# Debugger.net
KiCad netlist of a schematic drawn in Altium Designer
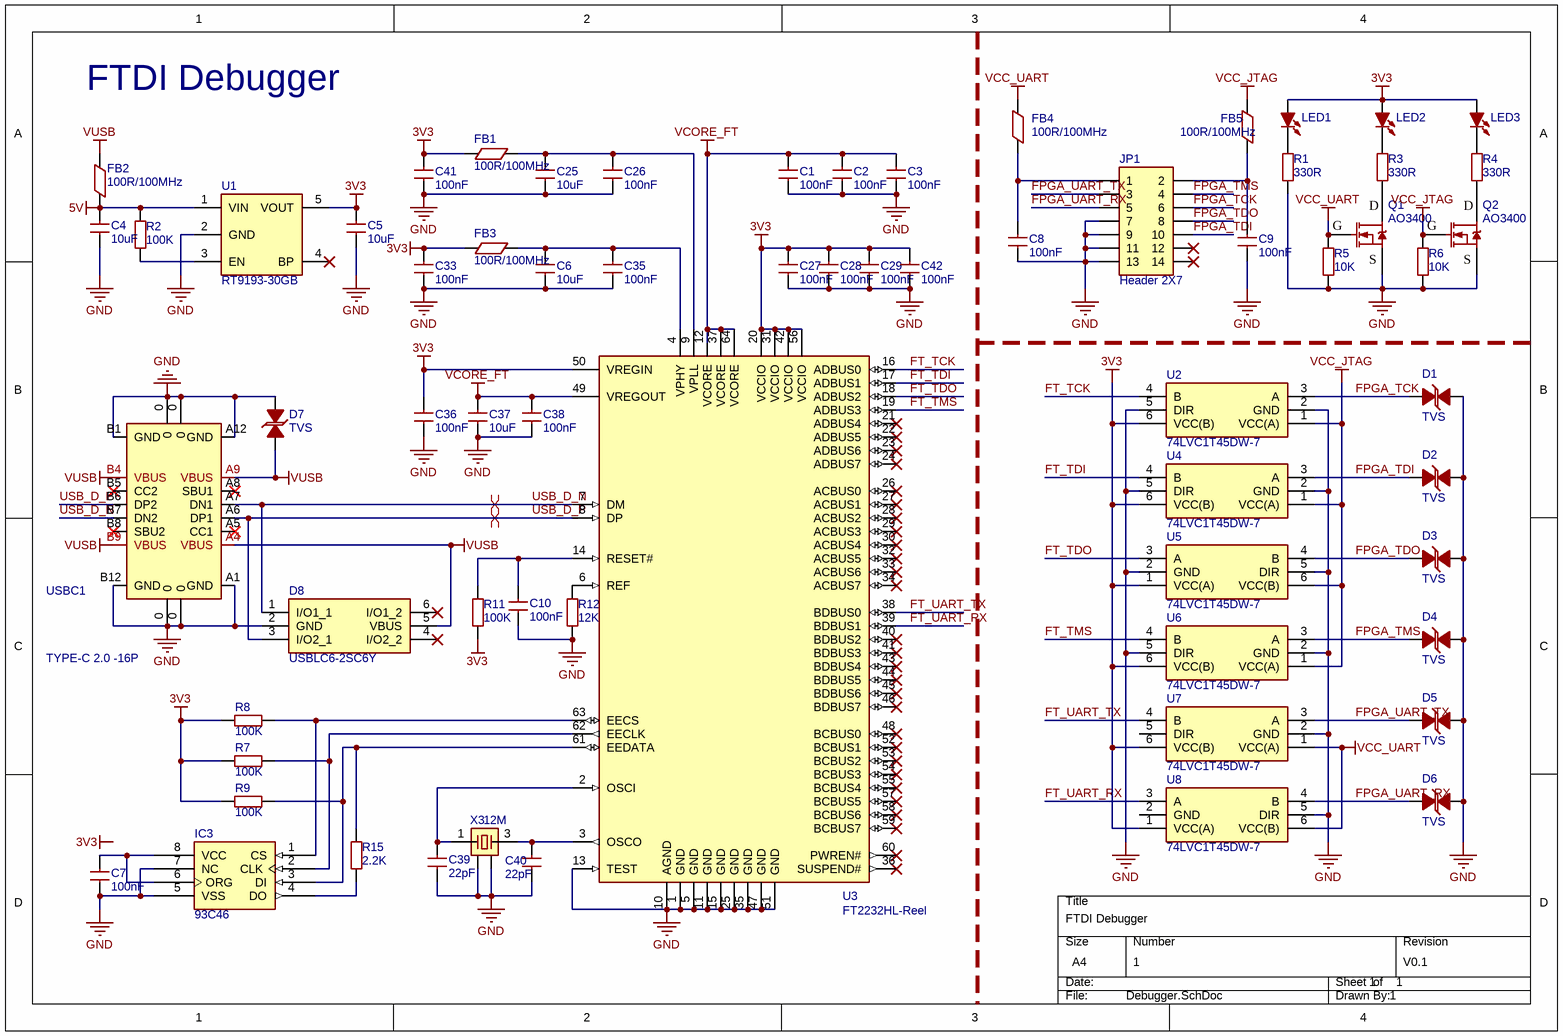
[diagram p0: Debugger.SchDoc]

(export (version "E")
  (design (tool "Eeschema 10.0.6"))
  (components
    (comp (ref "C1")
      (value "100nF")
      (footprint "C0603_NS")
      (description "贴片电容/MLCC电容")
      (libsource (lib "0.1 - 电阻-电容-电感-晶振-晶体-磁珠-电位器-法拉电容-馈通电容") (part "C"))
    )
    (comp (ref "C2")
      (value "100nF")
      (footprint "C0603_NS")
      (description "贴片电容/MLCC电容")
      (libsource (lib "0.1 - 电阻-电容-电感-晶振-晶体-磁珠-电位器-法拉电容-馈通电容") (part "C"))
    )
    (comp (ref "C3")
      (value "100nF")
      (footprint "C0603_NS")
      (description "贴片电容/MLCC电容")
      (libsource (lib "0.1 - 电阻-电容-电感-晶振-晶体-磁珠-电位器-法拉电容-馈通电容") (part "C"))
    )
    (comp (ref "C4")
      (value "10uF")
      (footprint "C0603_NS")
      (description "贴片电容/MLCC电容")
      (libsource (lib "0.1 - 电阻-电容-电感-晶振-晶体-磁珠-电位器-法拉电容-馈通电容") (part "C"))
    )
    (comp (ref "C5")
      (value "10uF")
      (footprint "C0603_NS")
      (description "贴片电容/MLCC电容")
      (libsource (lib "0.1 - 电阻-电容-电感-晶振-晶体-磁珠-电位器-法拉电容-馈通电容") (part "C"))
    )
    (comp (ref "C6")
      (value "10uF")
      (footprint "C0603_NS")
      (description "贴片电容/MLCC电容")
      (libsource (lib "0.1 - 电阻-电容-电感-晶振-晶体-磁珠-电位器-法拉电容-馈通电容") (part "C"))
    )
    (comp (ref "C7")
      (value "100nF")
      (footprint "C0603_NS")
      (description "贴片电容/MLCC电容")
      (libsource (lib "0.1 - 电阻-电容-电感-晶振-晶体-磁珠-电位器-法拉电容-馈通电容") (part "C"))
    )
    (comp (ref "C8")
      (value "100nF")
      (footprint "C0603_NS")
      (description "贴片电容/MLCC电容")
      (libsource (lib "0.1 - 电阻-电容-电感-晶振-晶体-磁珠-电位器-法拉电容-馈通电容") (part "C"))
    )
    (comp (ref "C9")
      (value "100nF")
      (footprint "C0603_NS")
      (description "贴片电容/MLCC电容")
      (libsource (lib "0.1 - 电阻-电容-电感-晶振-晶体-磁珠-电位器-法拉电容-馈通电容") (part "C"))
    )
    (comp (ref "C10")
      (value "100nF")
      (footprint "C0603_NS")
      (description "贴片电容/MLCC电容")
      (libsource (lib "0.1 - 电阻-电容-电感-晶振-晶体-磁珠-电位器-法拉电容-馈通电容") (part "C"))
    )
    (comp (ref "C25")
      (value "10uF")
      (footprint "C0603_NS")
      (description "贴片电容/MLCC电容")
      (libsource (lib "0.1 - 电阻-电容-电感-晶振-晶体-磁珠-电位器-法拉电容-馈通电容") (part "C"))
    )
    (comp (ref "C26")
      (value "100nF")
      (footprint "C0603_NS")
      (description "贴片电容/MLCC电容")
      (libsource (lib "0.1 - 电阻-电容-电感-晶振-晶体-磁珠-电位器-法拉电容-馈通电容") (part "C"))
    )
    (comp (ref "C27")
      (value "100nF")
      (footprint "C0603_NS")
      (description "贴片电容/MLCC电容")
      (libsource (lib "0.1 - 电阻-电容-电感-晶振-晶体-磁珠-电位器-法拉电容-馈通电容") (part "C"))
    )
    (comp (ref "C28")
      (value "100nF")
      (footprint "C0603_NS")
      (description "贴片电容/MLCC电容")
      (libsource (lib "0.1 - 电阻-电容-电感-晶振-晶体-磁珠-电位器-法拉电容-馈通电容") (part "C"))
    )
    (comp (ref "C29")
      (value "100nF")
      (footprint "C0603_NS")
      (description "贴片电容/MLCC电容")
      (libsource (lib "0.1 - 电阻-电容-电感-晶振-晶体-磁珠-电位器-法拉电容-馈通电容") (part "C"))
    )
    (comp (ref "C33")
      (value "100nF")
      (footprint "C0603_NS")
      (description "贴片电容/MLCC电容")
      (libsource (lib "0.1 - 电阻-电容-电感-晶振-晶体-磁珠-电位器-法拉电容-馈通电容") (part "C"))
    )
    (comp (ref "C35")
      (value "100nF")
      (footprint "C0603_NS")
      (description "贴片电容/MLCC电容")
      (libsource (lib "0.1 - 电阻-电容-电感-晶振-晶体-磁珠-电位器-法拉电容-馈通电容") (part "C"))
    )
    (comp (ref "C36")
      (value "100nF")
      (footprint "C0603_NS")
      (description "贴片电容/MLCC电容")
      (libsource (lib "0.1 - 电阻-电容-电感-晶振-晶体-磁珠-电位器-法拉电容-馈通电容") (part "C"))
    )
    (comp (ref "C37")
      (value "10uF")
      (footprint "C0603_NS")
      (description "贴片电容/MLCC电容")
      (libsource (lib "0.1 - 电阻-电容-电感-晶振-晶体-磁珠-电位器-法拉电容-馈通电容") (part "C"))
    )
    (comp (ref "C38")
      (value "100nF")
      (footprint "C0603_NS")
      (description "贴片电容/MLCC电容")
      (libsource (lib "0.1 - 电阻-电容-电感-晶振-晶体-磁珠-电位器-法拉电容-馈通电容") (part "C"))
    )
    (comp (ref "C39")
      (value "22pF")
      (footprint "C0603_NS")
      (description "贴片电容/MLCC电容")
      (libsource (lib "0.1 - 电阻-电容-电感-晶振-晶体-磁珠-电位器-法拉电容-馈通电容") (part "C"))
    )
    (comp (ref "C40")
      (value "22pF")
      (footprint "C0603_NS")
      (description "贴片电容/MLCC电容")
      (libsource (lib "0.1 - 电阻-电容-电感-晶振-晶体-磁珠-电位器-法拉电容-馈通电容") (part "C"))
    )
    (comp (ref "C41")
      (value "100nF")
      (footprint "C0603_NS")
      (description "贴片电容/MLCC电容")
      (libsource (lib "0.1 - 电阻-电容-电感-晶振-晶体-磁珠-电位器-法拉电容-馈通电容") (part "C"))
    )
    (comp (ref "C42")
      (value "100nF")
      (footprint "C0603_NS")
      (description "贴片电容/MLCC电容")
      (libsource (lib "0.1 - 电阻-电容-电感-晶振-晶体-磁珠-电位器-法拉电容-馈通电容") (part "C"))
    )
    (comp (ref "D1")
      (value "TVS")
      (footprint "SOD-123")
      (description "TVS通用")
      (libsource (lib "0.2 - 二极管-TVS-ESD-整流桥-放电管") (part "TVS"))
    )
    (comp (ref "D2")
      (value "TVS")
      (footprint "SOD-123")
      (description "TVS通用")
      (libsource (lib "0.2 - 二极管-TVS-ESD-整流桥-放电管") (part "TVS"))
    )
    (comp (ref "D3")
      (value "TVS")
      (footprint "SOD-123")
      (description "TVS通用")
      (libsource (lib "0.2 - 二极管-TVS-ESD-整流桥-放电管") (part "TVS"))
    )
    (comp (ref "D4")
      (value "TVS")
      (footprint "SOD-123")
      (description "TVS通用")
      (libsource (lib "0.2 - 二极管-TVS-ESD-整流桥-放电管") (part "TVS"))
    )
    (comp (ref "D5")
      (value "TVS")
      (footprint "SOD-123")
      (description "TVS通用")
      (libsource (lib "0.2 - 二极管-TVS-ESD-整流桥-放电管") (part "TVS"))
    )
    (comp (ref "D6")
      (value "TVS")
      (footprint "SOD-123")
      (description "TVS通用")
      (libsource (lib "0.2 - 二极管-TVS-ESD-整流桥-放电管") (part "TVS"))
    )
    (comp (ref "D7")
      (value "TVS")
      (footprint "SOD-123")
      (description "TVS通用")
      (libsource (lib "0.2 - 二极管-TVS-ESD-整流桥-放电管") (part "TVS"))
    )
    (comp (ref "D8")
      (value "USBLC6-2SC6Y")
      (footprint "SamacSys:SOT95P280X145-6N")
      (description "Diode")
      (fields (field (name "MOUSER PART NUMBER") "511-USBLC6-2SC6Y"))
      (libsource (lib "SamacSys") (part "USBLC6-2SC6Y"))
    )
    (comp (ref "FB1")
      (value "100R/100MHz")
      (footprint "R0805_L")
      (description "贴片磁珠")
      (libsource (lib "0.1 - 电阻-电容-电感-晶振-晶体-磁珠-电位器-法拉电容-馈通电容") (part "FB"))
    )
    (comp (ref "FB2")
      (value "100R/100MHz")
      (footprint "R0805_L")
      (description "贴片磁珠")
      (libsource (lib "0.1 - 电阻-电容-电感-晶振-晶体-磁珠-电位器-法拉电容-馈通电容") (part "FB"))
    )
    (comp (ref "FB3")
      (value "100R/100MHz")
      (footprint "R0805_L")
      (description "贴片磁珠")
      (libsource (lib "0.1 - 电阻-电容-电感-晶振-晶体-磁珠-电位器-法拉电容-馈通电容") (part "FB"))
    )
    (comp (ref "FB4")
      (value "100R/100MHz")
      (footprint "R0805_L")
      (description "贴片磁珠")
      (libsource (lib "0.1 - 电阻-电容-电感-晶振-晶体-磁珠-电位器-法拉电容-馈通电容") (part "FB"))
    )
    (comp (ref "FB5")
      (value "100R/100MHz")
      (footprint "R0805_L")
      (description "贴片磁珠")
      (libsource (lib "0.1 - 电阻-电容-电感-晶振-晶体-磁珠-电位器-法拉电容-馈通电容") (part "FB"))
    )
    (comp (ref "IC3")
      (value "93C46")
      (footprint "SOP8_L")
      (description "外置EEPROM")
      (libsource (lib "0.8 - 常见芯片") (part "93C46"))
    )
    (comp (ref "JP1")
      (value "Header 2X7")
      (footprint "HDR2.54-WI-2x7P")
      (description "7*2P接插件")
      (libsource (lib "5.5 - 2.54mm连接器(KF2EDGK_XH2.54_2.54排针排母)") (part "Header 7X2"))
    )
    (comp (ref "LED1")
      (value "红色")
      (footprint "LED0603_R")
      (description "贴片LED")
      (libsource (lib "0.3 - LED发光二极管-IR二极管_接收管-光耦") (part "LED-SMD"))
    )
    (comp (ref "LED2")
      (value "红色")
      (footprint "LED0603_R")
      (description "贴片LED")
      (libsource (lib "0.3 - LED发光二极管-IR二极管_接收管-光耦") (part "LED-SMD"))
    )
    (comp (ref "LED3")
      (value "红色")
      (footprint "LED0603_R")
      (description "贴片LED")
      (libsource (lib "0.3 - LED发光二极管-IR二极管_接收管-光耦") (part "LED-SMD"))
    )
    (comp (ref "Q1")
      (value "AO3400")
      (footprint "SOT23-3N")
      (description "N沟道 30V/4.2A")
      (libsource (lib "0.4 - 三极管-场效应管-可控硅") (part "AO3400"))
    )
    (comp (ref "Q2")
      (value "AO3400")
      (footprint "SOT23-3N")
      (description "N沟道 30V/4.2A")
      (libsource (lib "0.4 - 三极管-场效应管-可控硅") (part "AO3400"))
    )
    (comp (ref "R1")
      (value "330R")
      (footprint "R0603_NS")
      (description "贴片电阻")
      (libsource (lib "0.1 - 电阻-电容-电感-晶振-晶体-磁珠-电位器-法拉电容-馈通电容") (part "R"))
    )
    (comp (ref "R2")
      (value "100K")
      (footprint "R0603_NS")
      (description "贴片电阻")
      (libsource (lib "0.1 - 电阻-电容-电感-晶振-晶体-磁珠-电位器-法拉电容-馈通电容") (part "R"))
    )
    (comp (ref "R3")
      (value "330R")
      (footprint "R0603_NS")
      (description "贴片电阻")
      (libsource (lib "0.1 - 电阻-电容-电感-晶振-晶体-磁珠-电位器-法拉电容-馈通电容") (part "R"))
    )
    (comp (ref "R4")
      (value "330R")
      (footprint "R0603_NS")
      (description "贴片电阻")
      (libsource (lib "0.1 - 电阻-电容-电感-晶振-晶体-磁珠-电位器-法拉电容-馈通电容") (part "R"))
    )
    (comp (ref "R5")
      (value "10K")
      (footprint "R0603_NS")
      (description "贴片电阻")
      (libsource (lib "0.1 - 电阻-电容-电感-晶振-晶体-磁珠-电位器-法拉电容-馈通电容") (part "R"))
    )
    (comp (ref "R6")
      (value "10K")
      (footprint "R0603_NS")
      (description "贴片电阻")
      (libsource (lib "0.1 - 电阻-电容-电感-晶振-晶体-磁珠-电位器-法拉电容-馈通电容") (part "R"))
    )
    (comp (ref "R7")
      (value "100K")
      (footprint "R0603_NS")
      (description "贴片电阻")
      (libsource (lib "") (part "R_1"))
    )
    (comp (ref "R8")
      (value "100K")
      (footprint "R0603_NS")
      (description "贴片电阻")
      (libsource (lib "") (part "R_1"))
    )
    (comp (ref "R9")
      (value "100K")
      (footprint "R0603_NS")
      (description "贴片电阻")
      (libsource (lib "") (part "R_1"))
    )
    (comp (ref "R11")
      (value "100K")
      (footprint "R0603_NS")
      (description "贴片电阻")
      (libsource (lib "0.1 - 电阻-电容-电感-晶振-晶体-磁珠-电位器-法拉电容-馈通电容") (part "R"))
    )
    (comp (ref "R12")
      (value "12K")
      (footprint "R0603_NS")
      (description "贴片电阻")
      (libsource (lib "") (part "R_2"))
    )
    (comp (ref "R15")
      (value "2.2K")
      (footprint "R0603_NS")
      (description "贴片电阻")
      (libsource (lib "0.1 - 电阻-电容-电感-晶振-晶体-磁珠-电位器-法拉电容-馈通电容") (part "R"))
    )
    (comp (ref "U1")
      (value "RT9193-30GB")
      (footprint "SOT-23-5")
      (description "LDO 3.0V/0.3A")
      (libsource (lib "0.7 - 电源类芯片") (part "RT9193-30GB"))
    )
    (comp (ref "U2")
      (value "74LVC1T45DW-7")
      (footprint "SamacSys:SOT65P210X110-6N")
      (description "Undefined or Miscellaneous")
      (fields (field (name "MOUSER PART NUMBER") "621-74LVC1T45DW-7"))
      (libsource (lib "SamacSys") (part "74LVC1T45DW-7"))
    )
    (comp (ref "U3")
      (value "FT2232HL-Reel")
      (footprint "LQFP64-10*10")
      (description "Dual High Speed USB To Multipurpose UART/FIFO IC, 64-pin LQFP, Tape and Reel")
      (fields (field (name "MANUFACTURER") "FTDI"))
      (libsource (lib "8.1 - USB芯片") (part "CMP-0078-00023-3"))
    )
    (comp (ref "U4")
      (value "74LVC1T45DW-7")
      (footprint "SamacSys:SOT65P210X110-6N")
      (description "Undefined or Miscellaneous")
      (fields (field (name "MOUSER PART NUMBER") "621-74LVC1T45DW-7"))
      (libsource (lib "SamacSys") (part "74LVC1T45DW-7"))
    )
    (comp (ref "U5")
      (value "74LVC1T45DW-7")
      (footprint "SamacSys:SOT65P210X110-6N")
      (description "Undefined or Miscellaneous")
      (fields (field (name "MOUSER PART NUMBER") "621-74LVC1T45DW-7"))
      (libsource (lib "") (part "74LVC1T45DW-7_1"))
    )
    (comp (ref "U6")
      (value "74LVC1T45DW-7")
      (footprint "SamacSys:SOT65P210X110-6N")
      (description "Undefined or Miscellaneous")
      (fields (field (name "MOUSER PART NUMBER") "621-74LVC1T45DW-7"))
      (libsource (lib "SamacSys") (part "74LVC1T45DW-7"))
    )
    (comp (ref "U7")
      (value "74LVC1T45DW-7")
      (footprint "SamacSys:SOT65P210X110-6N")
      (description "Undefined or Miscellaneous")
      (fields (field (name "MOUSER PART NUMBER") "621-74LVC1T45DW-7"))
      (libsource (lib "SamacSys") (part "74LVC1T45DW-7"))
    )
    (comp (ref "U8")
      (value "74LVC1T45DW-7")
      (footprint "SamacSys:SOT65P210X110-6N")
      (description "Undefined or Miscellaneous")
      (fields (field (name "MOUSER PART NUMBER") "621-74LVC1T45DW-7"))
      (libsource (lib "") (part "74LVC1T45DW-7_1"))
    )
    (comp (ref "USBC1")
      (value "TYPE-C 2.0 -16P")
      (footprint "USB-C-SMD_16P")
      (description "USB2.0_Type-C_16Pin母座")
      (libsource (lib "0.6 - 电源_RJ45以太网_音频_SD-TF_SIM_ USB Type-C_HDMI插座") (part "USB2.0_Type-C_16Pin"))
    )
    (comp (ref "X3")
      (value "12M")
      (footprint "XTAL-3225-4P")
      (description "4脚无源晶振(谐振器）")
      (libsource (lib "0.1 - 电阻-电容-电感-晶振-晶体-磁珠-电位器-法拉电容-馈通电容") (part "XTAL-4P"))
    )
  )
  (nets
    (net (code "1") (name "/FPGA_TCK") (class "Default")
      (node (ref "D1") (pin "1") (pinfunction "A_1") (pintype "passive"))
      (node (ref "JP1") (pin "6") (pinfunction "6_6") (pintype "passive"))
      (node (ref "U2") (pin "3") (pinfunction "A_3") (pintype "passive"))
    )
    (net (code "2") (name "/FPGA_TDI") (class "Default")
      (node (ref "D2") (pin "1") (pinfunction "A_1") (pintype "passive"))
      (node (ref "JP1") (pin "10") (pinfunction "10_10") (pintype "passive"))
      (node (ref "U4") (pin "3") (pinfunction "A_3") (pintype "passive"))
    )
    (net (code "3") (name "/FPGA_TDO") (class "Default")
      (node (ref "D3") (pin "1") (pinfunction "A_1") (pintype "passive"))
      (node (ref "JP1") (pin "8") (pinfunction "8_8") (pintype "passive"))
      (node (ref "U5") (pin "4") (pinfunction "B_4") (pintype "passive"))
    )
    (net (code "4") (name "/FPGA_TMS") (class "Default")
      (node (ref "D4") (pin "1") (pinfunction "A_1") (pintype "passive"))
      (node (ref "JP1") (pin "4") (pinfunction "4_4") (pintype "passive"))
      (node (ref "U6") (pin "3") (pinfunction "A_3") (pintype "passive"))
    )
    (net (code "5") (name "/FPGA_UART_RX") (class "Default")
      (node (ref "D6") (pin "1") (pinfunction "A_1") (pintype "passive"))
      (node (ref "JP1") (pin "5") (pinfunction "5_5") (pintype "passive"))
      (node (ref "U8") (pin "4") (pinfunction "B_4") (pintype "passive"))
    )
    (net (code "6") (name "/FPGA_UART_TX") (class "Default")
      (node (ref "D5") (pin "1") (pinfunction "A_1") (pintype "passive"))
      (node (ref "JP1") (pin "3") (pinfunction "3_3") (pintype "passive"))
      (node (ref "U7") (pin "3") (pinfunction "A_3") (pintype "passive"))
    )
    (net (code "7") (name "/FT_TCK") (class "Default")
      (node (ref "U2") (pin "4") (pinfunction "B_4") (pintype "passive"))
      (node (ref "U3") (pin "16") (pinfunction "ADBUS0_16") (pintype "bidirectional"))
    )
    (net (code "8") (name "/FT_TDI") (class "Default")
      (node (ref "U3") (pin "17") (pinfunction "ADBUS1_17") (pintype "bidirectional"))
      (node (ref "U4") (pin "4") (pinfunction "B_4") (pintype "passive"))
    )
    (net (code "9") (name "/FT_TDO") (class "Default")
      (node (ref "U3") (pin "18") (pinfunction "ADBUS2_18") (pintype "bidirectional"))
      (node (ref "U5") (pin "3") (pinfunction "A_3") (pintype "passive"))
    )
    (net (code "10") (name "/FT_TMS") (class "Default")
      (node (ref "U3") (pin "19") (pinfunction "ADBUS3_19") (pintype "bidirectional"))
      (node (ref "U6") (pin "4") (pinfunction "B_4") (pintype "passive"))
    )
    (net (code "11") (name "/FT_UART_RX") (class "Default")
      (node (ref "U3") (pin "39") (pinfunction "BDBUS1_39") (pintype "bidirectional"))
      (node (ref "U8") (pin "3") (pinfunction "A_3") (pintype "passive"))
    )
    (net (code "12") (name "/FT_UART_TX") (class "Default")
      (node (ref "U3") (pin "38") (pinfunction "BDBUS0_38") (pintype "bidirectional"))
      (node (ref "U7") (pin "4") (pinfunction "B_4") (pintype "passive"))
    )
    (net (code "13") (name "/USB_D_N") (class "Default")
      (node (ref "D8") (pin "1") (pinfunction "I/O1_1_1") (pintype "passive"))
      (node (ref "U3") (pin "7") (pinfunction "DM_7") (pintype "input"))
      (node (ref "USBC1") (pin "A7") (pinfunction "DN1_A7") (pintype "passive"))
      (node (ref "USBC1") (pin "B7") (pinfunction "DN2_B7") (pintype "passive"))
    )
    (net (code "14") (name "/USB_D_P") (class "Default")
      (node (ref "D8") (pin "3") (pinfunction "I/O2_1_3") (pintype "passive"))
      (node (ref "U3") (pin "8") (pinfunction "DP_8") (pintype "input"))
      (node (ref "USBC1") (pin "A6") (pinfunction "DP1_A6") (pintype "passive"))
      (node (ref "USBC1") (pin "B6") (pinfunction "DP2_B6") (pintype "passive"))
    )
    (net (code "15") (name "3V3") (class "Default")
      (node (ref "C27") (pin "2") (pinfunction "2_2") (pintype "passive"))
      (node (ref "C28") (pin "2") (pinfunction "2_2") (pintype "passive"))
      (node (ref "C29") (pin "2") (pinfunction "2_2") (pintype "passive"))
      (node (ref "C33") (pin "2") (pinfunction "2_2") (pintype "passive"))
      (node (ref "C36") (pin "2") (pinfunction "2_2") (pintype "passive"))
      (node (ref "C41") (pin "2") (pinfunction "2_2") (pintype "passive"))
      (node (ref "C42") (pin "2") (pinfunction "2_2") (pintype "passive"))
      (node (ref "C5") (pin "1") (pinfunction "1_1") (pintype "passive"))
      (node (ref "FB1") (pin "1") (pinfunction "1_1") (pintype "passive"))
      (node (ref "FB3") (pin "1") (pinfunction "1_1") (pintype "passive"))
      (node (ref "LED1") (pin "1") (pinfunction "A_1") (pintype "passive"))
      (node (ref "LED2") (pin "1") (pinfunction "A_1") (pintype "passive"))
      (node (ref "LED3") (pin "1") (pinfunction "A_1") (pintype "passive"))
      (node (ref "R11") (pin "2") (pinfunction "2_2") (pintype "passive"))
      (node (ref "R7") (pin "2") (pinfunction "2_2") (pintype "passive"))
      (node (ref "R8") (pin "2") (pinfunction "2_2") (pintype "passive"))
      (node (ref "R9") (pin "2") (pinfunction "2_2") (pintype "passive"))
      (node (ref "U1") (pin "5") (pinfunction "VOUT_5") (pintype "passive"))
      (node (ref "U2") (pin "6") (pinfunction "VCC(B)_6") (pintype "passive"))
      (node (ref "U3") (pin "20") (pinfunction "VCCIO_20") (pintype "power_in"))
      (node (ref "U3") (pin "31") (pinfunction "VCCIO_31") (pintype "power_in"))
      (node (ref "U3") (pin "42") (pinfunction "VCCIO_42") (pintype "power_in"))
      (node (ref "U3") (pin "50") (pinfunction "VREGIN_50") (pintype "power_in"))
      (node (ref "U3") (pin "56") (pinfunction "VCCIO_56") (pintype "power_in"))
      (node (ref "U4") (pin "6") (pinfunction "VCC(B)_6") (pintype "passive"))
      (node (ref "U5") (pin "1") (pinfunction "VCC(A)_1") (pintype "passive"))
      (node (ref "U6") (pin "6") (pinfunction "VCC(B)_6") (pintype "passive"))
      (node (ref "U7") (pin "6") (pinfunction "VCC(B)_6") (pintype "passive"))
      (node (ref "U8") (pin "1") (pinfunction "VCC(A)_1") (pintype "passive"))
    )
    (net (code "16") (name "5V") (class "Default")
      (node (ref "C4") (pin "2") (pinfunction "2_2") (pintype "passive"))
      (node (ref "FB2") (pin "1") (pinfunction "1_1") (pintype "passive"))
      (node (ref "R2") (pin "1") (pinfunction "1_1") (pintype "passive"))
      (node (ref "U1") (pin "1") (pinfunction "VIN_1") (pintype "passive"))
    )
    (net (code "17") (name "GND") (class "Default")
      (node (ref "C1") (pin "1") (pinfunction "1_1") (pintype "passive"))
      (node (ref "C10") (pin "1") (pinfunction "1_1") (pintype "passive"))
      (node (ref "C2") (pin "1") (pinfunction "1_1") (pintype "passive"))
      (node (ref "C25") (pin "1") (pinfunction "1_1") (pintype "passive"))
      (node (ref "C26") (pin "1") (pinfunction "1_1") (pintype "passive"))
      (node (ref "C27") (pin "1") (pinfunction "1_1") (pintype "passive"))
      (node (ref "C28") (pin "1") (pinfunction "1_1") (pintype "passive"))
      (node (ref "C29") (pin "1") (pinfunction "1_1") (pintype "passive"))
      (node (ref "C3") (pin "1") (pinfunction "1_1") (pintype "passive"))
      (node (ref "C33") (pin "1") (pinfunction "1_1") (pintype "passive"))
      (node (ref "C35") (pin "1") (pinfunction "1_1") (pintype "passive"))
      (node (ref "C36") (pin "1") (pinfunction "1_1") (pintype "passive"))
      (node (ref "C37") (pin "1") (pinfunction "1_1") (pintype "passive"))
      (node (ref "C38") (pin "1") (pinfunction "1_1") (pintype "passive"))
      (node (ref "C39") (pin "1") (pinfunction "1_1") (pintype "passive"))
      (node (ref "C4") (pin "1") (pinfunction "1_1") (pintype "passive"))
      (node (ref "C40") (pin "1") (pinfunction "1_1") (pintype "passive"))
      (node (ref "C41") (pin "1") (pinfunction "1_1") (pintype "passive"))
      (node (ref "C42") (pin "1") (pinfunction "1_1") (pintype "passive"))
      (node (ref "C5") (pin "2") (pinfunction "2_2") (pintype "passive"))
      (node (ref "C6") (pin "1") (pinfunction "1_1") (pintype "passive"))
      (node (ref "C7") (pin "1") (pinfunction "1_1") (pintype "passive"))
      (node (ref "C8") (pin "1") (pinfunction "1_1") (pintype "passive"))
      (node (ref "C9") (pin "1") (pinfunction "1_1") (pintype "passive"))
      (node (ref "D1") (pin "2") (pinfunction "K_2") (pintype "passive"))
      (node (ref "D2") (pin "2") (pinfunction "K_2") (pintype "passive"))
      (node (ref "D3") (pin "2") (pinfunction "K_2") (pintype "passive"))
      (node (ref "D4") (pin "2") (pinfunction "K_2") (pintype "passive"))
      (node (ref "D5") (pin "2") (pinfunction "K_2") (pintype "passive"))
      (node (ref "D6") (pin "2") (pinfunction "K_2") (pintype "passive"))
      (node (ref "D7") (pin "1") (pinfunction "A_1") (pintype "passive"))
      (node (ref "D8") (pin "2") (pinfunction "GND_2") (pintype "passive"))
      (node (ref "IC3") (pin "5") (pinfunction "VSS_5") (pintype "passive"))
      (node (ref "IC3") (pin "7") (pinfunction "NC_7") (pintype "passive"))
      (node (ref "JP1") (pin "11") (pinfunction "11_11") (pintype "passive"))
      (node (ref "JP1") (pin "13") (pinfunction "13_13") (pintype "passive"))
      (node (ref "JP1") (pin "7") (pinfunction "7_7") (pintype "passive"))
      (node (ref "JP1") (pin "9") (pinfunction "9_9") (pintype "passive"))
      (node (ref "Q1") (pin "2") (pinfunction "S_2") (pintype "passive"))
      (node (ref "Q2") (pin "2") (pinfunction "S_2") (pintype "passive"))
      (node (ref "R1") (pin "2") (pinfunction "2_2") (pintype "passive"))
      (node (ref "R12") (pin "1") (pinfunction "1_1") (pintype "passive"))
      (node (ref "R5") (pin "2") (pinfunction "2_2") (pintype "passive"))
      (node (ref "R6") (pin "2") (pinfunction "2_2") (pintype "passive"))
      (node (ref "U1") (pin "2") (pinfunction "GND_2") (pintype "passive"))
      (node (ref "U2") (pin "2") (pinfunction "GND_2") (pintype "passive"))
      (node (ref "U2") (pin "5") (pinfunction "DIR_5") (pintype "passive"))
      (node (ref "U3") (pin "1") (pinfunction "GND_1") (pintype "power_in"))
      (node (ref "U3") (pin "10") (pinfunction "AGND_10") (pintype "power_in"))
      (node (ref "U3") (pin "11") (pinfunction "GND_11") (pintype "power_in"))
      (node (ref "U3") (pin "13") (pinfunction "TEST_13") (pintype "input"))
      (node (ref "U3") (pin "15") (pinfunction "GND_15") (pintype "power_in"))
      (node (ref "U3") (pin "25") (pinfunction "GND_25") (pintype "power_in"))
      (node (ref "U3") (pin "35") (pinfunction "GND_35") (pintype "power_in"))
      (node (ref "U3") (pin "47") (pinfunction "GND_47") (pintype "power_in"))
      (node (ref "U3") (pin "5") (pinfunction "GND_5") (pintype "power_in"))
      (node (ref "U3") (pin "51") (pinfunction "GND_51") (pintype "power_in"))
      (node (ref "U4") (pin "2") (pinfunction "GND_2") (pintype "passive"))
      (node (ref "U4") (pin "5") (pinfunction "DIR_5") (pintype "passive"))
      (node (ref "U5") (pin "2") (pinfunction "GND_2") (pintype "passive"))
      (node (ref "U5") (pin "5") (pinfunction "DIR_5") (pintype "passive"))
      (node (ref "U6") (pin "2") (pinfunction "GND_2") (pintype "passive"))
      (node (ref "U6") (pin "5") (pinfunction "DIR_5") (pintype "passive"))
      (node (ref "U7") (pin "2") (pinfunction "GND_2") (pintype "passive"))
      (node (ref "U8") (pin "5") (pinfunction "DIR_5") (pintype "passive"))
      (node (ref "USBC1") (pin "0") (pinfunction "0_0") (pintype "passive"))
      (node (ref "USBC1") (pin "A1") (pinfunction "GND_A1") (pintype "passive"))
      (node (ref "USBC1") (pin "A12") (pinfunction "GND_A12") (pintype "passive"))
      (node (ref "USBC1") (pin "B1") (pinfunction "GND_B1") (pintype "passive"))
      (node (ref "USBC1") (pin "B12") (pinfunction "GND_B12") (pintype "passive"))
      (node (ref "X3") (pin "2") (pinfunction "2_2") (pintype "passive"))
      (node (ref "X3") (pin "4") (pinfunction "4_4") (pintype "passive"))
    )
    (net (code "18") (name "Net-(C8-Pad2)") (class "Default")
      (node (ref "C8") (pin "2") (pinfunction "2_2") (pintype "passive"))
      (node (ref "FB4") (pin "1") (pinfunction "1_1") (pintype "passive"))
      (node (ref "JP1") (pin "1") (pinfunction "1_1") (pintype "passive"))
    )
    (net (code "19") (name "Net-(C9-Pad2)") (class "Default")
      (node (ref "C9") (pin "2") (pinfunction "2_2") (pintype "passive"))
      (node (ref "FB5") (pin "1") (pinfunction "1_1") (pintype "passive"))
      (node (ref "JP1") (pin "2") (pinfunction "2_2") (pintype "passive"))
    )
    (net (code "20") (name "Net-(IC3-CLK)") (class "Default")
      (node (ref "IC3") (pin "2") (pinfunction "CLK_2") (pintype "input"))
      (node (ref "R7") (pin "1") (pinfunction "1_1") (pintype "passive"))
      (node (ref "U3") (pin "62") (pinfunction "EECLK_62") (pintype "output"))
    )
    (net (code "21") (name "Net-(IC3-CS)") (class "Default")
      (node (ref "IC3") (pin "1") (pinfunction "CS_1") (pintype "input"))
      (node (ref "R8") (pin "1") (pinfunction "1_1") (pintype "passive"))
      (node (ref "U3") (pin "63") (pinfunction "EECS_63") (pintype "bidirectional"))
    )
    (net (code "22") (name "Net-(IC3-DI)") (class "Default")
      (node (ref "IC3") (pin "3") (pinfunction "DI_3") (pintype "input"))
      (node (ref "R15") (pin "1") (pinfunction "1_1") (pintype "passive"))
      (node (ref "R9") (pin "1") (pinfunction "1_1") (pintype "passive"))
      (node (ref "U3") (pin "61") (pinfunction "EEDATA_61") (pintype "bidirectional"))
    )
    (net (code "23") (name "Net-(IC3-DO)") (class "Default")
      (node (ref "IC3") (pin "4") (pinfunction "DO_4") (pintype "output"))
      (node (ref "R15") (pin "2") (pinfunction "2_2") (pintype "passive"))
    )
    (net (code "24") (name "Net-(IC3-ORG)") (class "Default")
      (node (ref "C7") (pin "2") (pinfunction "2_2") (pintype "passive"))
      (node (ref "IC3") (pin "6") (pinfunction "ORG_6") (pintype "passive"))
      (node (ref "IC3") (pin "8") (pinfunction "VCC_8") (pintype "power_in"))
    )
    (net (code "25") (name "Net-(LED1-K)") (class "Default")
      (node (ref "LED1") (pin "2") (pinfunction "K_2") (pintype "passive"))
      (node (ref "R1") (pin "1") (pinfunction "1_1") (pintype "passive"))
    )
    (net (code "26") (name "Net-(LED2-K)") (class "Default")
      (node (ref "LED2") (pin "2") (pinfunction "K_2") (pintype "passive"))
      (node (ref "R3") (pin "1") (pinfunction "1_1") (pintype "passive"))
    )
    (net (code "27") (name "Net-(LED3-K)") (class "Default")
      (node (ref "LED3") (pin "2") (pinfunction "K_2") (pintype "passive"))
      (node (ref "R4") (pin "1") (pinfunction "1_1") (pintype "passive"))
    )
    (net (code "28") (name "Net-(Q1-D)") (class "Default")
      (node (ref "Q1") (pin "3") (pinfunction "D_3") (pintype "passive"))
      (node (ref "R3") (pin "2") (pinfunction "2_2") (pintype "passive"))
    )
    (net (code "29") (name "Net-(Q2-D)") (class "Default")
      (node (ref "Q2") (pin "3") (pinfunction "D_3") (pintype "passive"))
      (node (ref "R4") (pin "2") (pinfunction "2_2") (pintype "passive"))
    )
    (net (code "30") (name "Net-(U1-EN)") (class "Default")
      (node (ref "R2") (pin "2") (pinfunction "2_2") (pintype "passive"))
      (node (ref "U1") (pin "3") (pinfunction "EN_3") (pintype "passive"))
    )
    (net (code "31") (name "Net-(U3-OSCI)") (class "Default")
      (node (ref "C39") (pin "2") (pinfunction "2_2") (pintype "passive"))
      (node (ref "U3") (pin "2") (pinfunction "OSCI_2") (pintype "input"))
      (node (ref "X3") (pin "1") (pinfunction "1_1") (pintype "passive"))
    )
    (net (code "32") (name "Net-(U3-OSCO)") (class "Default")
      (node (ref "C40") (pin "2") (pinfunction "2_2") (pintype "passive"))
      (node (ref "U3") (pin "3") (pinfunction "OSCO_3") (pintype "output"))
      (node (ref "X3") (pin "3") (pinfunction "3_3") (pintype "passive"))
    )
    (net (code "33") (name "Net-(U3-REF)") (class "Default")
      (node (ref "R12") (pin "2") (pinfunction "2_2") (pintype "passive"))
      (node (ref "U3") (pin "6") (pinfunction "REF_6") (pintype "input"))
    )
    (net (code "34") (name "Net-(U3-RESET#)") (class "Default")
      (node (ref "C10") (pin "2") (pinfunction "2_2") (pintype "passive"))
      (node (ref "R11") (pin "1") (pinfunction "1_1") (pintype "passive"))
      (node (ref "U3") (pin "14") (pinfunction "RESET#_14") (pintype "input"))
    )
    (net (code "35") (name "Net-(U3-VPHY)") (class "Default")
      (node (ref "C35") (pin "2") (pinfunction "2_2") (pintype "passive"))
      (node (ref "C6") (pin "2") (pinfunction "2_2") (pintype "passive"))
      (node (ref "FB3") (pin "2") (pinfunction "2_2") (pintype "passive"))
      (node (ref "U3") (pin "4") (pinfunction "VPHY_4") (pintype "power_in"))
    )
    (net (code "36") (name "Net-(U3-VPLL)") (class "Default")
      (node (ref "C25") (pin "2") (pinfunction "2_2") (pintype "passive"))
      (node (ref "C26") (pin "2") (pinfunction "2_2") (pintype "passive"))
      (node (ref "FB1") (pin "2") (pinfunction "2_2") (pintype "passive"))
      (node (ref "U3") (pin "9") (pinfunction "VPLL_9") (pintype "power_in"))
    )
    (net (code "37") (name "VCC_JTAG") (class "Default")
      (node (ref "FB5") (pin "2") (pinfunction "2_2") (pintype "passive"))
      (node (ref "Q2") (pin "1") (pinfunction "G_1") (pintype "passive"))
      (node (ref "R6") (pin "1") (pinfunction "1_1") (pintype "passive"))
      (node (ref "U2") (pin "1") (pinfunction "VCC(A)_1") (pintype "passive"))
      (node (ref "U4") (pin "1") (pinfunction "VCC(A)_1") (pintype "passive"))
      (node (ref "U5") (pin "6") (pinfunction "VCC(B)_6") (pintype "passive"))
      (node (ref "U6") (pin "1") (pinfunction "VCC(A)_1") (pintype "passive"))
    )
    (net (code "38") (name "VCC_UART") (class "Default")
      (node (ref "FB4") (pin "2") (pinfunction "2_2") (pintype "passive"))
      (node (ref "Q1") (pin "1") (pinfunction "G_1") (pintype "passive"))
      (node (ref "R5") (pin "1") (pinfunction "1_1") (pintype "passive"))
      (node (ref "U7") (pin "1") (pinfunction "VCC(A)_1") (pintype "passive"))
      (node (ref "U8") (pin "6") (pinfunction "VCC(B)_6") (pintype "passive"))
    )
    (net (code "39") (name "VCORE_FT") (class "Default")
      (node (ref "C1") (pin "2") (pinfunction "2_2") (pintype "passive"))
      (node (ref "C2") (pin "2") (pinfunction "2_2") (pintype "passive"))
      (node (ref "C3") (pin "2") (pinfunction "2_2") (pintype "passive"))
      (node (ref "C37") (pin "2") (pinfunction "2_2") (pintype "passive"))
      (node (ref "C38") (pin "2") (pinfunction "2_2") (pintype "passive"))
      (node (ref "U3") (pin "12") (pinfunction "VCORE_12") (pintype "power_in"))
      (node (ref "U3") (pin "37") (pinfunction "VCORE_37") (pintype "power_in"))
      (node (ref "U3") (pin "49") (pinfunction "VREGOUT_49") (pintype "power_in"))
      (node (ref "U3") (pin "64") (pinfunction "VCORE_64") (pintype "power_in"))
    )
    (net (code "40") (name "VUSB") (class "Default")
      (node (ref "D7") (pin "2") (pinfunction "K_2") (pintype "passive"))
      (node (ref "D8") (pin "5") (pinfunction "VBUS_5") (pintype "passive"))
      (node (ref "FB2") (pin "2") (pinfunction "2_2") (pintype "passive"))
      (node (ref "USBC1") (pin "A4") (pinfunction "VBUS_A4") (pintype "passive"))
      (node (ref "USBC1") (pin "A9") (pinfunction "VBUS_A9") (pintype "passive"))
      (node (ref "USBC1") (pin "B4") (pinfunction "VBUS_B4") (pintype "passive"))
      (node (ref "USBC1") (pin "B9") (pinfunction "VBUS_B9") (pintype "passive"))
    )
    (net (code "41") (name "unconnected-(D8-I{slash}O1_2-Pad6)") (class "Default")
      (node (ref "D8") (pin "6") (pinfunction "I/O1_2_6") (pintype "passive+no_connect"))
    )
    (net (code "42") (name "unconnected-(D8-I{slash}O2_2-Pad4)") (class "Default")
      (node (ref "D8") (pin "4") (pinfunction "I/O2_2_4") (pintype "passive+no_connect"))
    )
    (net (code "43") (name "unconnected-(JP1-Pad12)") (class "Default")
      (node (ref "JP1") (pin "12") (pinfunction "12_12") (pintype "passive+no_connect"))
    )
    (net (code "44") (name "unconnected-(JP1-Pad14)") (class "Default")
      (node (ref "JP1") (pin "14") (pinfunction "14_14") (pintype "passive+no_connect"))
    )
    (net (code "45") (name "unconnected-(U1-BP-Pad4)") (class "Default")
      (node (ref "U1") (pin "4") (pinfunction "BP_4") (pintype "passive+no_connect"))
    )
    (net (code "46") (name "unconnected-(U3-ACBUS0-Pad26)") (class "Default")
      (node (ref "U3") (pin "26") (pinfunction "ACBUS0_26") (pintype "bidirectional+no_connect"))
    )
    (net (code "47") (name "unconnected-(U3-ACBUS1-Pad27)") (class "Default")
      (node (ref "U3") (pin "27") (pinfunction "ACBUS1_27") (pintype "bidirectional+no_connect"))
    )
    (net (code "48") (name "unconnected-(U3-ACBUS2-Pad28)") (class "Default")
      (node (ref "U3") (pin "28") (pinfunction "ACBUS2_28") (pintype "bidirectional+no_connect"))
    )
    (net (code "49") (name "unconnected-(U3-ACBUS3-Pad29)") (class "Default")
      (node (ref "U3") (pin "29") (pinfunction "ACBUS3_29") (pintype "bidirectional+no_connect"))
    )
    (net (code "50") (name "unconnected-(U3-ACBUS4-Pad30)") (class "Default")
      (node (ref "U3") (pin "30") (pinfunction "ACBUS4_30") (pintype "bidirectional+no_connect"))
    )
    (net (code "51") (name "unconnected-(U3-ACBUS5-Pad32)") (class "Default")
      (node (ref "U3") (pin "32") (pinfunction "ACBUS5_32") (pintype "bidirectional+no_connect"))
    )
    (net (code "52") (name "unconnected-(U3-ACBUS6-Pad33)") (class "Default")
      (node (ref "U3") (pin "33") (pinfunction "ACBUS6_33") (pintype "bidirectional+no_connect"))
    )
    (net (code "53") (name "unconnected-(U3-ACBUS7-Pad34)") (class "Default")
      (node (ref "U3") (pin "34") (pinfunction "ACBUS7_34") (pintype "bidirectional+no_connect"))
    )
    (net (code "54") (name "unconnected-(U3-ADBUS4-Pad21)") (class "Default")
      (node (ref "U3") (pin "21") (pinfunction "ADBUS4_21") (pintype "bidirectional+no_connect"))
    )
    (net (code "55") (name "unconnected-(U3-ADBUS5-Pad22)") (class "Default")
      (node (ref "U3") (pin "22") (pinfunction "ADBUS5_22") (pintype "bidirectional+no_connect"))
    )
    (net (code "56") (name "unconnected-(U3-ADBUS6-Pad23)") (class "Default")
      (node (ref "U3") (pin "23") (pinfunction "ADBUS6_23") (pintype "bidirectional+no_connect"))
    )
    (net (code "57") (name "unconnected-(U3-ADBUS7-Pad24)") (class "Default")
      (node (ref "U3") (pin "24") (pinfunction "ADBUS7_24") (pintype "bidirectional+no_connect"))
    )
    (net (code "58") (name "unconnected-(U3-BCBUS0-Pad48)") (class "Default")
      (node (ref "U3") (pin "48") (pinfunction "BCBUS0_48") (pintype "bidirectional+no_connect"))
    )
    (net (code "59") (name "unconnected-(U3-BCBUS1-Pad52)") (class "Default")
      (node (ref "U3") (pin "52") (pinfunction "BCBUS1_52") (pintype "bidirectional+no_connect"))
    )
    (net (code "60") (name "unconnected-(U3-BCBUS2-Pad53)") (class "Default")
      (node (ref "U3") (pin "53") (pinfunction "BCBUS2_53") (pintype "bidirectional+no_connect"))
    )
    (net (code "61") (name "unconnected-(U3-BCBUS3-Pad54)") (class "Default")
      (node (ref "U3") (pin "54") (pinfunction "BCBUS3_54") (pintype "bidirectional+no_connect"))
    )
    (net (code "62") (name "unconnected-(U3-BCBUS4-Pad55)") (class "Default")
      (node (ref "U3") (pin "55") (pinfunction "BCBUS4_55") (pintype "bidirectional+no_connect"))
    )
    (net (code "63") (name "unconnected-(U3-BCBUS5-Pad57)") (class "Default")
      (node (ref "U3") (pin "57") (pinfunction "BCBUS5_57") (pintype "bidirectional+no_connect"))
    )
    (net (code "64") (name "unconnected-(U3-BCBUS6-Pad58)") (class "Default")
      (node (ref "U3") (pin "58") (pinfunction "BCBUS6_58") (pintype "bidirectional+no_connect"))
    )
    (net (code "65") (name "unconnected-(U3-BCBUS7-Pad59)") (class "Default")
      (node (ref "U3") (pin "59") (pinfunction "BCBUS7_59") (pintype "bidirectional+no_connect"))
    )
    (net (code "66") (name "unconnected-(U3-BDBUS2-Pad40)") (class "Default")
      (node (ref "U3") (pin "40") (pinfunction "BDBUS2_40") (pintype "bidirectional+no_connect"))
    )
    (net (code "67") (name "unconnected-(U3-BDBUS3-Pad41)") (class "Default")
      (node (ref "U3") (pin "41") (pinfunction "BDBUS3_41") (pintype "bidirectional+no_connect"))
    )
    (net (code "68") (name "unconnected-(U3-BDBUS4-Pad43)") (class "Default")
      (node (ref "U3") (pin "43") (pinfunction "BDBUS4_43") (pintype "bidirectional+no_connect"))
    )
    (net (code "69") (name "unconnected-(U3-BDBUS5-Pad44)") (class "Default")
      (node (ref "U3") (pin "44") (pinfunction "BDBUS5_44") (pintype "bidirectional+no_connect"))
    )
    (net (code "70") (name "unconnected-(U3-BDBUS6-Pad45)") (class "Default")
      (node (ref "U3") (pin "45") (pinfunction "BDBUS6_45") (pintype "bidirectional+no_connect"))
    )
    (net (code "71") (name "unconnected-(U3-BDBUS7-Pad46)") (class "Default")
      (node (ref "U3") (pin "46") (pinfunction "BDBUS7_46") (pintype "bidirectional+no_connect"))
    )
    (net (code "72") (name "unconnected-(U3-PWREN#-Pad60)") (class "Default")
      (node (ref "U3") (pin "60") (pinfunction "PWREN#_60") (pintype "output+no_connect"))
    )
    (net (code "73") (name "unconnected-(U3-SUSPEND#-Pad36)") (class "Default")
      (node (ref "U3") (pin "36") (pinfunction "SUSPEND#_36") (pintype "output+no_connect"))
    )
    (net (code "74") (name "unconnected-(U7-DIR-Pad5)") (class "Default")
      (node (ref "U7") (pin "5") (pinfunction "DIR_5") (pintype "passive"))
    )
    (net (code "75") (name "unconnected-(U8-GND-Pad2)") (class "Default")
      (node (ref "U8") (pin "2") (pinfunction "GND_2") (pintype "passive"))
    )
    (net (code "76") (name "unconnected-(USBC1-CC1-PadA5)") (class "Default")
      (node (ref "USBC1") (pin "A5") (pinfunction "CC1_A5") (pintype "passive+no_connect"))
    )
    (net (code "77") (name "unconnected-(USBC1-CC2-PadB5)") (class "Default")
      (node (ref "USBC1") (pin "B5") (pinfunction "CC2_B5") (pintype "passive+no_connect"))
    )
    (net (code "78") (name "unconnected-(USBC1-SBU1-PadA8)") (class "Default")
      (node (ref "USBC1") (pin "A8") (pinfunction "SBU1_A8") (pintype "passive+no_connect"))
    )
    (net (code "79") (name "unconnected-(USBC1-SBU2-PadB8)") (class "Default")
      (node (ref "USBC1") (pin "B8") (pinfunction "SBU2_B8") (pintype "passive+no_connect"))
    )
  )
)
